# LED_debug.net
KiCad netlist of a schematic drawn in Altium Designer
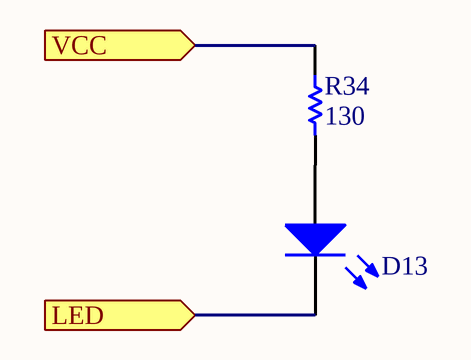
[diagram p0: LED_debug.SchDoc]

(export (version "E")
  (design (tool "Eeschema 10.0.6"))
  (components
    (comp (ref "D13")
      (value "LED - NORMAL LED")
      (footprint "LED-0603 GREEN")
      (libsource (lib "CHINOOK_LIBRARY") (part "LED - NORMAL LED"))
    )
    (comp (ref "R34")
      (value "130")
      (footprint "RS-0603")
      (fields
        (field (name "POWER") "RES POWER")
        (field (name "TOLERANCE") "RES TOL")
        (field (name "Comment") "RS - RESISTOR")
      )
      (libsource (lib "CHINOOK_LIBRARY") (part "RS - RESISTOR"))
    )
  )
  (nets
    (net (code "1") (name "/LED") (class "Default")
      (node (ref "D13") (pin "K") (pinfunction "K_K") (pintype "passive"))
    )
    (net (code "2") (name "/VCC") (class "Default")
      (node (ref "R34") (pin "1") (pinfunction "1_1") (pintype "passive"))
    )
    (net (code "3") (name "Net-(D13-PadA)") (class "Default")
      (node (ref "D13") (pin "A") (pinfunction "A_A") (pintype "passive"))
      (node (ref "R34") (pin "2") (pinfunction "2_2") (pintype "passive"))
    )
  )
)
